# IVSTAGEV2.net
KiCad netlist of a schematic drawn in EAGLE
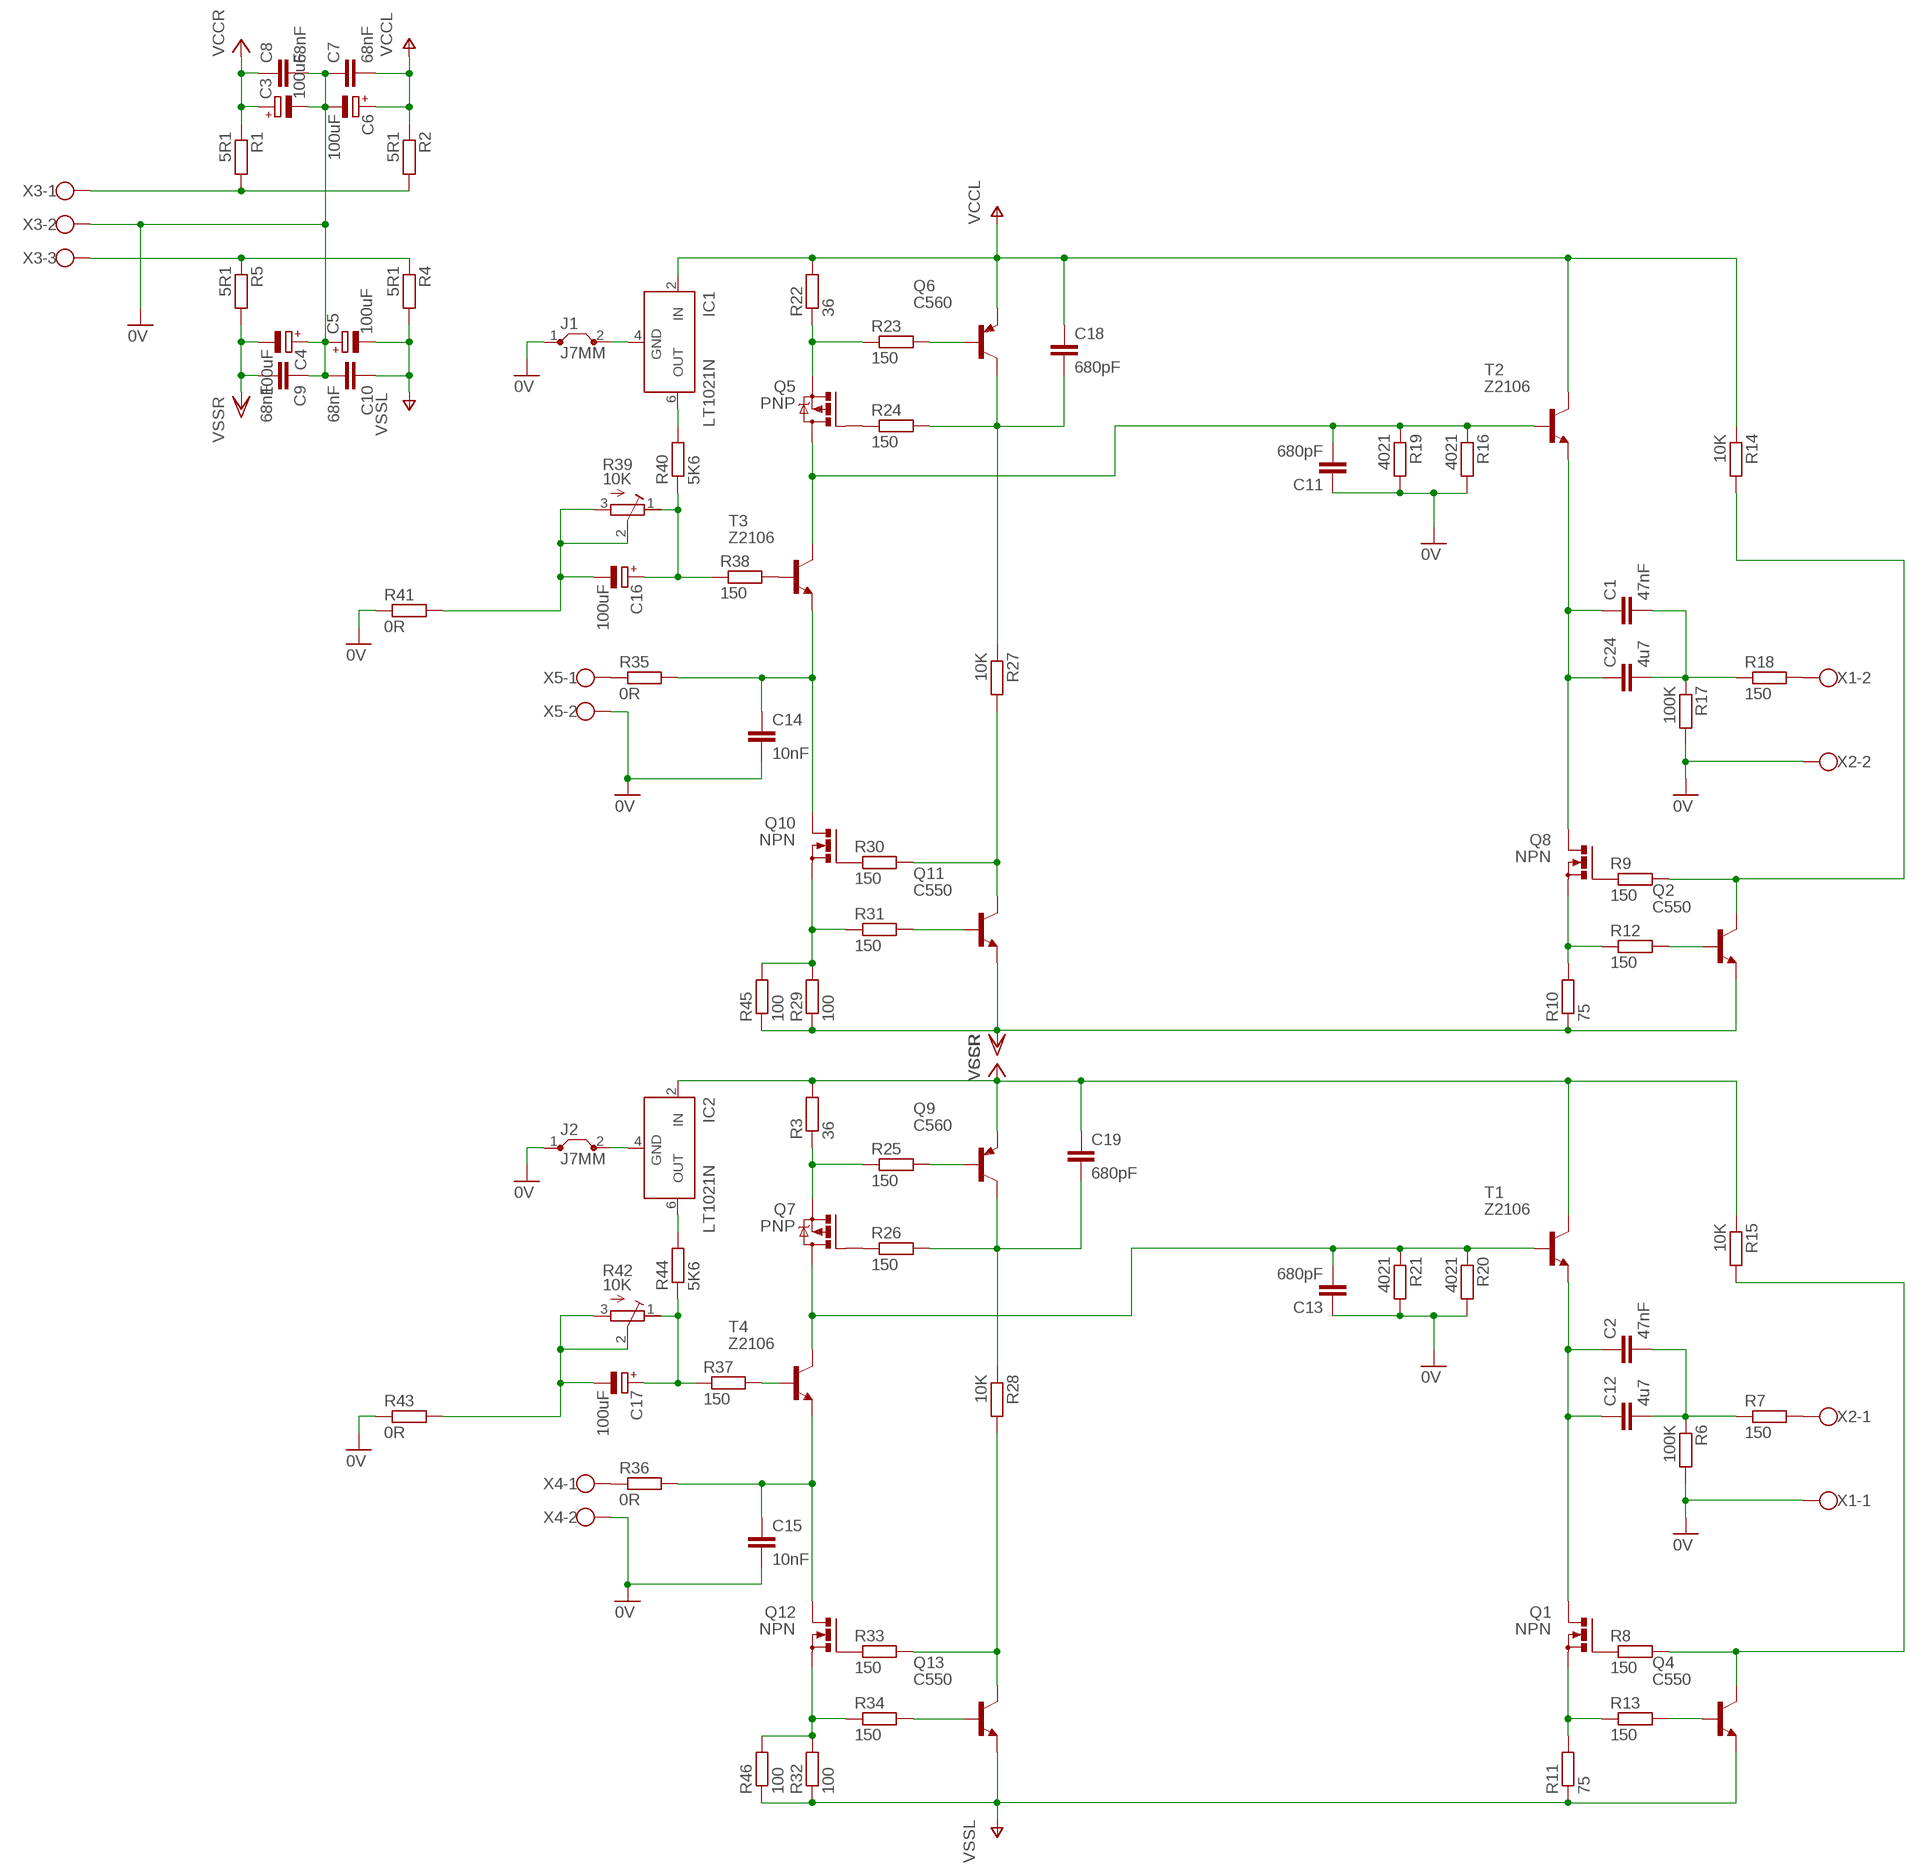
[diagram p0: schematic, sheet 1]

(export (version "E")
  (design (tool "Eeschema 10.0.6"))
  (components
    (comp (ref "C1")
      (value "47nF")
      (footprint "eagle-import:C050-050X075")
      (libsource (lib "eagle-import") (part "C-EU050-050X075"))
    )
    (comp (ref "C2")
      (value "47nF")
      (footprint "eagle-import:C050-050X075")
      (libsource (lib "eagle-import") (part "C-EU050-050X075"))
    )
    (comp (ref "C3")
      (value "100uF")
      (footprint "eagle-import:E5-13")
      (libsource (lib "eagle-import") (part "CPOL-EUE5-13"))
    )
    (comp (ref "C4")
      (value "100uF")
      (footprint "eagle-import:E5-13")
      (libsource (lib "eagle-import") (part "CPOL-EUE5-13"))
    )
    (comp (ref "C5")
      (value "100uF")
      (footprint "eagle-import:E5-13")
      (libsource (lib "eagle-import") (part "CPOL-EUE5-13"))
    )
    (comp (ref "C6")
      (value "100uF")
      (footprint "eagle-import:E5-13")
      (libsource (lib "eagle-import") (part "CPOL-EUE5-13"))
    )
    (comp (ref "C7")
      (value "68nF")
      (footprint "eagle-import:C050-035X075")
      (libsource (lib "eagle-import") (part "C-EU050-035X075"))
    )
    (comp (ref "C8")
      (value "68nF")
      (footprint "eagle-import:C050-035X075")
      (libsource (lib "eagle-import") (part "C-EU050-035X075"))
    )
    (comp (ref "C9")
      (value "68nF")
      (footprint "eagle-import:C050-035X075")
      (libsource (lib "eagle-import") (part "C-EU050-035X075"))
    )
    (comp (ref "C10")
      (value "68nF")
      (footprint "eagle-import:C050-035X075")
      (libsource (lib "eagle-import") (part "C-EU050-035X075"))
    )
    (comp (ref "C11")
      (value "680pF")
      (footprint "eagle-import:C050-035X075")
      (libsource (lib "eagle-import") (part "C-EU050-035X075"))
    )
    (comp (ref "C12")
      (value "4u7")
      (footprint "eagle-import:C37.5B19")
      (libsource (lib "eagle-import") (part "C37/19"))
    )
    (comp (ref "C13")
      (value "680pF")
      (footprint "eagle-import:C050-035X075")
      (libsource (lib "eagle-import") (part "C-EU050-035X075"))
    )
    (comp (ref "C14")
      (value "10nF")
      (footprint "eagle-import:C050-050X075")
      (libsource (lib "eagle-import") (part "C-EU050-050X075"))
    )
    (comp (ref "C15")
      (value "10nF")
      (footprint "eagle-import:C050-050X075")
      (libsource (lib "eagle-import") (part "C-EU050-050X075"))
    )
    (comp (ref "C16")
      (value "100uF")
      (footprint "eagle-import:E5-10,5")
      (libsource (lib "eagle-import") (part "CPOL-EUE5-10.5"))
    )
    (comp (ref "C17")
      (value "100uF")
      (footprint "eagle-import:E5-10,5")
      (libsource (lib "eagle-import") (part "CPOL-EUE5-10.5"))
    )
    (comp (ref "C18")
      (value "680pF")
      (footprint "eagle-import:C050-045X075")
      (libsource (lib "eagle-import") (part "C-EU050-045X075"))
    )
    (comp (ref "C19")
      (value "680pF")
      (footprint "eagle-import:C050-045X075")
      (libsource (lib "eagle-import") (part "C-EU050-045X075"))
    )
    (comp (ref "C24")
      (value "4u7")
      (footprint "eagle-import:C37.5B19")
      (libsource (lib "eagle-import") (part "C37/19"))
    )
    (comp (ref "IC1")
      (value "LT1021N")
      (footprint "eagle-import:DIL08")
      (libsource (lib "eagle-import") (part "LT1021N"))
    )
    (comp (ref "IC2")
      (value "LT1021N")
      (footprint "eagle-import:DIL08")
      (libsource (lib "eagle-import") (part "LT1021N"))
    )
    (comp (ref "J1")
      (value "J7MM")
      (footprint "eagle-import:07")
      (libsource (lib "eagle-import") (part "J7MM"))
    )
    (comp (ref "J2")
      (value "J7MM")
      (footprint "eagle-import:07")
      (libsource (lib "eagle-import") (part "J7MM"))
    )
    (comp (ref "Q1")
      (value "NPN")
      (footprint "eagle-import:TO220BV")
      (libsource (lib "eagle-import") (part "PMOSFET_NTO220BV"))
    )
    (comp (ref "Q2")
      (value "C550")
      (footprint "eagle-import:TO92-EBC")
      (libsource (lib "eagle-import") (part "BC550B"))
    )
    (comp (ref "Q4")
      (value "C550")
      (footprint "eagle-import:TO92-EBC")
      (libsource (lib "eagle-import") (part "BC550B"))
    )
    (comp (ref "Q5")
      (value "PNP")
      (footprint "eagle-import:TO220BV")
      (libsource (lib "eagle-import") (part "IRF9530"))
    )
    (comp (ref "Q6")
      (value "C560")
      (footprint "eagle-import:TO92-EBC")
      (libsource (lib "eagle-import") (part "BC560"))
    )
    (comp (ref "Q7")
      (value "PNP")
      (footprint "eagle-import:TO220BV")
      (libsource (lib "eagle-import") (part "IRF9530"))
    )
    (comp (ref "Q8")
      (value "NPN")
      (footprint "eagle-import:TO220BV")
      (libsource (lib "eagle-import") (part "PMOSFET_NTO220BV"))
    )
    (comp (ref "Q9")
      (value "C560")
      (footprint "eagle-import:TO92-EBC")
      (libsource (lib "eagle-import") (part "BC560"))
    )
    (comp (ref "Q10")
      (value "NPN")
      (footprint "eagle-import:TO220BV")
      (libsource (lib "eagle-import") (part "PMOSFET_NTO220BV"))
    )
    (comp (ref "Q11")
      (value "C550")
      (footprint "eagle-import:TO92-EBC")
      (libsource (lib "eagle-import") (part "BC550B"))
    )
    (comp (ref "Q12")
      (value "NPN")
      (footprint "eagle-import:TO220BV")
      (libsource (lib "eagle-import") (part "PMOSFET_NTO220BV"))
    )
    (comp (ref "Q13")
      (value "C550")
      (footprint "eagle-import:TO92-EBC")
      (libsource (lib "eagle-import") (part "BC550B"))
    )
    (comp (ref "R1")
      (value "5R1")
      (footprint "eagle-import:0207_7")
      (libsource (lib "eagle-import") (part "R-EU_0207/7"))
    )
    (comp (ref "R2")
      (value "5R1")
      (footprint "eagle-import:0207_7")
      (libsource (lib "eagle-import") (part "R-EU_0207/7"))
    )
    (comp (ref "R3")
      (value "36")
      (footprint "eagle-import:0207_7")
      (libsource (lib "eagle-import") (part "R-EU_0207/7"))
    )
    (comp (ref "R4")
      (value "5R1")
      (footprint "eagle-import:0207_7")
      (libsource (lib "eagle-import") (part "R-EU_0207/7"))
    )
    (comp (ref "R5")
      (value "5R1")
      (footprint "eagle-import:0207_7")
      (libsource (lib "eagle-import") (part "R-EU_0207/7"))
    )
    (comp (ref "R6")
      (value "100K")
      (footprint "eagle-import:0204_7")
      (libsource (lib "eagle-import") (part "R-EU_0204/7"))
    )
    (comp (ref "R7")
      (value "150")
      (footprint "eagle-import:0207_7")
      (libsource (lib "eagle-import") (part "R-EU_0207/7"))
    )
    (comp (ref "R8")
      (value "150")
      (footprint "eagle-import:0207_7")
      (libsource (lib "eagle-import") (part "R-EU_0207/7"))
    )
    (comp (ref "R9")
      (value "150")
      (footprint "eagle-import:0207_7")
      (libsource (lib "eagle-import") (part "R-EU_0207/7"))
    )
    (comp (ref "R10")
      (value "75")
      (footprint "eagle-import:0207_7")
      (libsource (lib "eagle-import") (part "R-EU_0207/7"))
    )
    (comp (ref "R11")
      (value "75")
      (footprint "eagle-import:0207_7")
      (libsource (lib "eagle-import") (part "R-EU_0207/7"))
    )
    (comp (ref "R12")
      (value "150")
      (footprint "eagle-import:0207_7")
      (libsource (lib "eagle-import") (part "R-EU_0207/7"))
    )
    (comp (ref "R13")
      (value "150")
      (footprint "eagle-import:0207_7")
      (libsource (lib "eagle-import") (part "R-EU_0207/7"))
    )
    (comp (ref "R14")
      (value "10K")
      (footprint "eagle-import:0309_12")
      (libsource (lib "eagle-import") (part "R-EU_0309/12"))
    )
    (comp (ref "R15")
      (value "10K")
      (footprint "eagle-import:0309_12")
      (libsource (lib "eagle-import") (part "R-EU_0309/12"))
    )
    (comp (ref "R16")
      (value "4021")
      (footprint "eagle-import:0309_12")
      (libsource (lib "eagle-import") (part "R-EU_0309/12"))
    )
    (comp (ref "R17")
      (value "100K")
      (footprint "eagle-import:0204_7")
      (libsource (lib "eagle-import") (part "R-EU_0204/7"))
    )
    (comp (ref "R18")
      (value "150")
      (footprint "eagle-import:0207_7")
      (libsource (lib "eagle-import") (part "R-EU_0207/7"))
    )
    (comp (ref "R19")
      (value "4021")
      (footprint "eagle-import:0309_12")
      (libsource (lib "eagle-import") (part "R-EU_0309/12"))
    )
    (comp (ref "R20")
      (value "4021")
      (footprint "eagle-import:0309_12")
      (libsource (lib "eagle-import") (part "R-EU_0309/12"))
    )
    (comp (ref "R21")
      (value "4021")
      (footprint "eagle-import:0309_12")
      (libsource (lib "eagle-import") (part "R-EU_0309/12"))
    )
    (comp (ref "R22")
      (value "36")
      (footprint "eagle-import:0207_7")
      (libsource (lib "eagle-import") (part "R-EU_0207/7"))
    )
    (comp (ref "R23")
      (value "150")
      (footprint "eagle-import:0207_10")
      (libsource (lib "eagle-import") (part "R-EU_0207/10"))
    )
    (comp (ref "R24")
      (value "150")
      (footprint "eagle-import:0207_7")
      (libsource (lib "eagle-import") (part "R-EU_0207/7"))
    )
    (comp (ref "R25")
      (value "150")
      (footprint "eagle-import:0207_10")
      (libsource (lib "eagle-import") (part "R-EU_0207/10"))
    )
    (comp (ref "R26")
      (value "150")
      (footprint "eagle-import:0207_10")
      (libsource (lib "eagle-import") (part "R-EU_0207/10"))
    )
    (comp (ref "R27")
      (value "10K")
      (footprint "eagle-import:0309_12")
      (libsource (lib "eagle-import") (part "R-EU_0309/12"))
    )
    (comp (ref "R28")
      (value "10K")
      (footprint "eagle-import:0309_12")
      (libsource (lib "eagle-import") (part "R-EU_0309/12"))
    )
    (comp (ref "R29")
      (value "100")
      (footprint "eagle-import:0207_7")
      (libsource (lib "eagle-import") (part "R-EU_0207/7"))
    )
    (comp (ref "R30")
      (value "150")
      (footprint "eagle-import:0207_7")
      (libsource (lib "eagle-import") (part "R-EU_0207/7"))
    )
    (comp (ref "R31")
      (value "150")
      (footprint "eagle-import:0207_7")
      (libsource (lib "eagle-import") (part "R-EU_0207/7"))
    )
    (comp (ref "R32")
      (value "100")
      (footprint "eagle-import:0207_7")
      (libsource (lib "eagle-import") (part "R-EU_0207/7"))
    )
    (comp (ref "R33")
      (value "150")
      (footprint "eagle-import:0207_7")
      (libsource (lib "eagle-import") (part "R-EU_0207/7"))
    )
    (comp (ref "R34")
      (value "150")
      (footprint "eagle-import:0207_7")
      (libsource (lib "eagle-import") (part "R-EU_0207/7"))
    )
    (comp (ref "R35")
      (value "0R")
      (footprint "eagle-import:0207_7")
      (libsource (lib "eagle-import") (part "R-EU_0207/7"))
    )
    (comp (ref "R36")
      (value "0R")
      (footprint "eagle-import:0207_7")
      (libsource (lib "eagle-import") (part "R-EU_0207/7"))
    )
    (comp (ref "R37")
      (value "150")
      (footprint "eagle-import:0204_7")
      (libsource (lib "eagle-import") (part "R-EU_0204/7"))
    )
    (comp (ref "R38")
      (value "150")
      (footprint "eagle-import:0204_7")
      (libsource (lib "eagle-import") (part "R-EU_0204/7"))
    )
    (comp (ref "R39")
      (value "10K")
      (footprint "eagle-import:RTRIMT93YA")
      (libsource (lib "eagle-import") (part "R-TRIMMT93YA"))
    )
    (comp (ref "R40")
      (value "5K6")
      (footprint "eagle-import:0207_10")
      (libsource (lib "eagle-import") (part "R-EU_0207/10"))
    )
    (comp (ref "R41")
      (value "0R")
      (footprint "eagle-import:0207_10")
      (libsource (lib "eagle-import") (part "R-EU_0207/10"))
    )
    (comp (ref "R42")
      (value "10K")
      (footprint "eagle-import:RTRIMT93YA")
      (libsource (lib "eagle-import") (part "R-TRIMMT93YA"))
    )
    (comp (ref "R43")
      (value "0R")
      (footprint "eagle-import:0207_10")
      (libsource (lib "eagle-import") (part "R-EU_0207/10"))
    )
    (comp (ref "R44")
      (value "5K6")
      (footprint "eagle-import:0207_10")
      (libsource (lib "eagle-import") (part "R-EU_0207/10"))
    )
    (comp (ref "R45")
      (value "100")
      (footprint "eagle-import:0207_7")
      (libsource (lib "eagle-import") (part "R-EU_0207/7"))
    )
    (comp (ref "R46")
      (value "100")
      (footprint "eagle-import:0207_7")
      (libsource (lib "eagle-import") (part "R-EU_0207/7"))
    )
    (comp (ref "T1")
      (value "Z2106")
      (footprint "eagle-import:TO92-EBC")
      (libsource (lib "eagle-import") (part "-NPN-TO92-EBCBC337"))
    )
    (comp (ref "T2")
      (value "Z2106")
      (footprint "eagle-import:TO92-EBC")
      (libsource (lib "eagle-import") (part "-NPN-TO92-EBCBC337-40"))
    )
    (comp (ref "T3")
      (value "Z2106")
      (footprint "eagle-import:TO92-EBC")
      (libsource (lib "eagle-import") (part "-NPN-TO92-EBCBC337"))
    )
    (comp (ref "T4")
      (value "Z2106")
      (footprint "eagle-import:TO92-EBC")
      (libsource (lib "eagle-import") (part "-NPN-TO92-EBCBC337-40"))
    )
    (comp (ref "X1")
      (value "W237-02P")
      (footprint "eagle-import:W237-132")
      (libsource (lib "eagle-import") (part "W237-02P"))
    )
    (comp (ref "X2")
      (value "W237-02P")
      (footprint "eagle-import:W237-132")
      (libsource (lib "eagle-import") (part "W237-02P"))
    )
    (comp (ref "X3")
      (value "W237-03P")
      (footprint "eagle-import:W237-133")
      (libsource (lib "eagle-import") (part "W237-03P"))
    )
    (comp (ref "X4")
      (value "W237-02P")
      (footprint "eagle-import:W237-132")
      (libsource (lib "eagle-import") (part "W237-02P"))
    )
    (comp (ref "X5")
      (value "W237-02P")
      (footprint "eagle-import:W237-132")
      (libsource (lib "eagle-import") (part "W237-02P"))
    )
  )
  (nets
    (net (code "1") (name "0V") (class "Default")
      (node (ref "C10") (pin "2") (pinfunction "2_2") (pintype "passive"))
      (node (ref "C11") (pin "1") (pinfunction "1_1") (pintype "passive"))
      (node (ref "C13") (pin "1") (pinfunction "1_1") (pintype "passive"))
      (node (ref "C14") (pin "2") (pinfunction "2_2") (pintype "passive"))
      (node (ref "C15") (pin "2") (pinfunction "2_2") (pintype "passive"))
      (node (ref "C3") (pin "-") (pinfunction "-_-") (pintype "passive"))
      (node (ref "C4") (pin "+") (pinfunction "+_+") (pintype "passive"))
      (node (ref "C5") (pin "+") (pinfunction "+_+") (pintype "passive"))
      (node (ref "C6") (pin "-") (pinfunction "-_-") (pintype "passive"))
      (node (ref "C7") (pin "1") (pinfunction "1_1") (pintype "passive"))
      (node (ref "C8") (pin "2") (pinfunction "2_2") (pintype "passive"))
      (node (ref "C9") (pin "1") (pinfunction "1_1") (pintype "passive"))
      (node (ref "J1") (pin "1") (pinfunction "1_1") (pintype "passive"))
      (node (ref "J2") (pin "1") (pinfunction "1_1") (pintype "passive"))
      (node (ref "R16") (pin "2") (pinfunction "2_2") (pintype "passive"))
      (node (ref "R17") (pin "2") (pinfunction "2_2") (pintype "passive"))
      (node (ref "R19") (pin "2") (pinfunction "2_2") (pintype "passive"))
      (node (ref "R20") (pin "2") (pinfunction "2_2") (pintype "passive"))
      (node (ref "R21") (pin "2") (pinfunction "2_2") (pintype "passive"))
      (node (ref "R41") (pin "1") (pinfunction "1_1") (pintype "passive"))
      (node (ref "R43") (pin "1") (pinfunction "1_1") (pintype "passive"))
      (node (ref "R6") (pin "2") (pinfunction "2_2") (pintype "passive"))
      (node (ref "X1") (pin "1") (pinfunction "KL_1") (pintype "passive"))
      (node (ref "X2") (pin "2") (pinfunction "KL_2") (pintype "passive"))
      (node (ref "X3") (pin "2") (pinfunction "KL_2") (pintype "passive"))
      (node (ref "X4") (pin "2") (pinfunction "KL_2") (pintype "passive"))
      (node (ref "X5") (pin "2") (pinfunction "KL_2") (pintype "passive"))
    )
    (net (code "2") (name "Net-(C1-Pad1)") (class "Default")
      (node (ref "C1") (pin "1") (pinfunction "1_1") (pintype "passive"))
      (node (ref "C24") (pin "1") (pinfunction "1_1") (pintype "passive"))
      (node (ref "Q8") (pin "D") (pinfunction "D_D") (pintype "passive"))
      (node (ref "T2") (pin "E") (pinfunction "E_E") (pintype "passive"))
    )
    (net (code "3") (name "Net-(C1-Pad2)") (class "Default")
      (node (ref "C1") (pin "2") (pinfunction "2_2") (pintype "passive"))
      (node (ref "C24") (pin "2") (pinfunction "2_2") (pintype "passive"))
      (node (ref "R17") (pin "1") (pinfunction "1_1") (pintype "passive"))
      (node (ref "R18") (pin "1") (pinfunction "1_1") (pintype "passive"))
    )
    (net (code "4") (name "Net-(C11-Pad2)") (class "Default")
      (node (ref "C11") (pin "2") (pinfunction "2_2") (pintype "passive"))
      (node (ref "Q5") (pin "D") (pinfunction "D_D") (pintype "passive"))
      (node (ref "R16") (pin "1") (pinfunction "1_1") (pintype "passive"))
      (node (ref "R19") (pin "1") (pinfunction "1_1") (pintype "passive"))
      (node (ref "T2") (pin "B") (pinfunction "B_B") (pintype "passive"))
      (node (ref "T3") (pin "C") (pinfunction "C_C") (pintype "passive"))
    )
    (net (code "5") (name "Net-(C12-Pad1)") (class "Default")
      (node (ref "C12") (pin "1") (pinfunction "1_1") (pintype "passive"))
      (node (ref "C2") (pin "1") (pinfunction "1_1") (pintype "passive"))
      (node (ref "Q1") (pin "D") (pinfunction "D_D") (pintype "passive"))
      (node (ref "T1") (pin "E") (pinfunction "E_E") (pintype "passive"))
    )
    (net (code "6") (name "Net-(C12-Pad2)") (class "Default")
      (node (ref "C12") (pin "2") (pinfunction "2_2") (pintype "passive"))
      (node (ref "C2") (pin "2") (pinfunction "2_2") (pintype "passive"))
      (node (ref "R6") (pin "1") (pinfunction "1_1") (pintype "passive"))
      (node (ref "R7") (pin "1") (pinfunction "1_1") (pintype "passive"))
    )
    (net (code "7") (name "Net-(C13-Pad2)") (class "Default")
      (node (ref "C13") (pin "2") (pinfunction "2_2") (pintype "passive"))
      (node (ref "Q7") (pin "D") (pinfunction "D_D") (pintype "passive"))
      (node (ref "R20") (pin "1") (pinfunction "1_1") (pintype "passive"))
      (node (ref "R21") (pin "1") (pinfunction "1_1") (pintype "passive"))
      (node (ref "T1") (pin "B") (pinfunction "B_B") (pintype "passive"))
      (node (ref "T4") (pin "C") (pinfunction "C_C") (pintype "passive"))
    )
    (net (code "8") (name "Net-(C14-Pad1)") (class "Default")
      (node (ref "C14") (pin "1") (pinfunction "1_1") (pintype "passive"))
      (node (ref "Q10") (pin "D") (pinfunction "D_D") (pintype "passive"))
      (node (ref "R35") (pin "2") (pinfunction "2_2") (pintype "passive"))
      (node (ref "T3") (pin "E") (pinfunction "E_E") (pintype "passive"))
    )
    (net (code "9") (name "Net-(C15-Pad1)") (class "Default")
      (node (ref "C15") (pin "1") (pinfunction "1_1") (pintype "passive"))
      (node (ref "Q12") (pin "D") (pinfunction "D_D") (pintype "passive"))
      (node (ref "R36") (pin "2") (pinfunction "2_2") (pintype "passive"))
      (node (ref "T4") (pin "E") (pinfunction "E_E") (pintype "passive"))
    )
    (net (code "10") (name "Net-(C18-Pad2)") (class "Default")
      (node (ref "C18") (pin "2") (pinfunction "2_2") (pintype "passive"))
      (node (ref "Q6") (pin "C") (pinfunction "C_C") (pintype "passive"))
      (node (ref "R24") (pin "2") (pinfunction "2_2") (pintype "passive"))
      (node (ref "R27") (pin "1") (pinfunction "1_1") (pintype "passive"))
    )
    (net (code "11") (name "Net-(C19-Pad2)") (class "Default")
      (node (ref "C19") (pin "2") (pinfunction "2_2") (pintype "passive"))
      (node (ref "Q9") (pin "C") (pinfunction "C_C") (pintype "passive"))
      (node (ref "R26") (pin "2") (pinfunction "2_2") (pintype "passive"))
      (node (ref "R28") (pin "1") (pinfunction "1_1") (pintype "passive"))
    )
    (net (code "12") (name "Net-(IC1-GND)") (class "Default")
      (node (ref "IC1") (pin "4") (pinfunction "GND_4") (pintype "power_in"))
      (node (ref "J1") (pin "2") (pinfunction "2_2") (pintype "passive"))
    )
    (net (code "13") (name "Net-(IC1-OUT)") (class "Default")
      (node (ref "IC1") (pin "6") (pinfunction "OUT_6") (pintype "output"))
      (node (ref "R40") (pin "2") (pinfunction "2_2") (pintype "passive"))
    )
    (net (code "14") (name "Net-(IC2-GND)") (class "Default")
      (node (ref "IC2") (pin "4") (pinfunction "GND_4") (pintype "power_in"))
      (node (ref "J2") (pin "2") (pinfunction "2_2") (pintype "passive"))
    )
    (net (code "15") (name "Net-(IC2-OUT)") (class "Default")
      (node (ref "IC2") (pin "6") (pinfunction "OUT_6") (pintype "output"))
      (node (ref "R44") (pin "2") (pinfunction "2_2") (pintype "passive"))
    )
    (net (code "16") (name "Net-(Q1-PadG)") (class "Default")
      (node (ref "Q1") (pin "G") (pinfunction "G_G") (pintype "passive"))
      (node (ref "R8") (pin "1") (pinfunction "1_1") (pintype "passive"))
    )
    (net (code "17") (name "Net-(Q1-PadS)") (class "Default")
      (node (ref "Q1") (pin "S") (pinfunction "S_S") (pintype "passive"))
      (node (ref "R11") (pin "2") (pinfunction "2_2") (pintype "passive"))
      (node (ref "R13") (pin "1") (pinfunction "1_1") (pintype "passive"))
    )
    (net (code "18") (name "Net-(Q2-PadB)") (class "Default")
      (node (ref "Q2") (pin "B") (pinfunction "B_B") (pintype "passive"))
      (node (ref "R12") (pin "2") (pinfunction "2_2") (pintype "passive"))
    )
    (net (code "19") (name "Net-(Q2-PadC)") (class "Default")
      (node (ref "Q2") (pin "C") (pinfunction "C_C") (pintype "passive"))
      (node (ref "R14") (pin "2") (pinfunction "2_2") (pintype "passive"))
      (node (ref "R9") (pin "2") (pinfunction "2_2") (pintype "passive"))
    )
    (net (code "20") (name "Net-(Q4-PadB)") (class "Default")
      (node (ref "Q4") (pin "B") (pinfunction "B_B") (pintype "passive"))
      (node (ref "R13") (pin "2") (pinfunction "2_2") (pintype "passive"))
    )
    (net (code "21") (name "Net-(Q4-PadC)") (class "Default")
      (node (ref "Q4") (pin "C") (pinfunction "C_C") (pintype "passive"))
      (node (ref "R15") (pin "2") (pinfunction "2_2") (pintype "passive"))
      (node (ref "R8") (pin "2") (pinfunction "2_2") (pintype "passive"))
    )
    (net (code "22") (name "Net-(Q5-PadG)") (class "Default")
      (node (ref "Q5") (pin "G") (pinfunction "G_G") (pintype "passive"))
      (node (ref "R24") (pin "1") (pinfunction "1_1") (pintype "passive"))
    )
    (net (code "23") (name "Net-(Q5-PadS)") (class "Default")
      (node (ref "Q5") (pin "S") (pinfunction "S_S") (pintype "passive"))
      (node (ref "R22") (pin "1") (pinfunction "1_1") (pintype "passive"))
      (node (ref "R23") (pin "1") (pinfunction "1_1") (pintype "passive"))
    )
    (net (code "24") (name "Net-(Q6-PadB)") (class "Default")
      (node (ref "Q6") (pin "B") (pinfunction "B_B") (pintype "passive"))
      (node (ref "R23") (pin "2") (pinfunction "2_2") (pintype "passive"))
    )
    (net (code "25") (name "Net-(Q7-PadG)") (class "Default")
      (node (ref "Q7") (pin "G") (pinfunction "G_G") (pintype "passive"))
      (node (ref "R26") (pin "1") (pinfunction "1_1") (pintype "passive"))
    )
    (net (code "26") (name "Net-(Q7-PadS)") (class "Default")
      (node (ref "Q7") (pin "S") (pinfunction "S_S") (pintype "passive"))
      (node (ref "R25") (pin "1") (pinfunction "1_1") (pintype "passive"))
      (node (ref "R3") (pin "1") (pinfunction "1_1") (pintype "passive"))
    )
    (net (code "27") (name "Net-(Q8-PadG)") (class "Default")
      (node (ref "Q8") (pin "G") (pinfunction "G_G") (pintype "passive"))
      (node (ref "R9") (pin "1") (pinfunction "1_1") (pintype "passive"))
    )
    (net (code "28") (name "Net-(Q8-PadS)") (class "Default")
      (node (ref "Q8") (pin "S") (pinfunction "S_S") (pintype "passive"))
      (node (ref "R10") (pin "2") (pinfunction "2_2") (pintype "passive"))
      (node (ref "R12") (pin "1") (pinfunction "1_1") (pintype "passive"))
    )
    (net (code "29") (name "Net-(Q9-PadB)") (class "Default")
      (node (ref "Q9") (pin "B") (pinfunction "B_B") (pintype "passive"))
      (node (ref "R25") (pin "2") (pinfunction "2_2") (pintype "passive"))
    )
    (net (code "30") (name "Net-(Q10-PadG)") (class "Default")
      (node (ref "Q10") (pin "G") (pinfunction "G_G") (pintype "passive"))
      (node (ref "R30") (pin "1") (pinfunction "1_1") (pintype "passive"))
    )
    (net (code "31") (name "Net-(Q10-PadS)") (class "Default")
      (node (ref "Q10") (pin "S") (pinfunction "S_S") (pintype "passive"))
      (node (ref "R29") (pin "2") (pinfunction "2_2") (pintype "passive"))
      (node (ref "R31") (pin "1") (pinfunction "1_1") (pintype "passive"))
      (node (ref "R45") (pin "2") (pinfunction "2_2") (pintype "passive"))
    )
    (net (code "32") (name "Net-(Q11-PadB)") (class "Default")
      (node (ref "Q11") (pin "B") (pinfunction "B_B") (pintype "passive"))
      (node (ref "R31") (pin "2") (pinfunction "2_2") (pintype "passive"))
    )
    (net (code "33") (name "Net-(Q11-PadC)") (class "Default")
      (node (ref "Q11") (pin "C") (pinfunction "C_C") (pintype "passive"))
      (node (ref "R27") (pin "2") (pinfunction "2_2") (pintype "passive"))
      (node (ref "R30") (pin "2") (pinfunction "2_2") (pintype "passive"))
    )
    (net (code "34") (name "Net-(Q12-PadG)") (class "Default")
      (node (ref "Q12") (pin "G") (pinfunction "G_G") (pintype "passive"))
      (node (ref "R33") (pin "1") (pinfunction "1_1") (pintype "passive"))
    )
    (net (code "35") (name "Net-(Q12-PadS)") (class "Default")
      (node (ref "Q12") (pin "S") (pinfunction "S_S") (pintype "passive"))
      (node (ref "R32") (pin "2") (pinfunction "2_2") (pintype "passive"))
      (node (ref "R34") (pin "1") (pinfunction "1_1") (pintype "passive"))
      (node (ref "R46") (pin "2") (pinfunction "2_2") (pintype "passive"))
    )
    (net (code "36") (name "Net-(Q13-PadB)") (class "Default")
      (node (ref "Q13") (pin "B") (pinfunction "B_B") (pintype "passive"))
      (node (ref "R34") (pin "2") (pinfunction "2_2") (pintype "passive"))
    )
    (net (code "37") (name "Net-(Q13-PadC)") (class "Default")
      (node (ref "Q13") (pin "C") (pinfunction "C_C") (pintype "passive"))
      (node (ref "R28") (pin "2") (pinfunction "2_2") (pintype "passive"))
      (node (ref "R33") (pin "2") (pinfunction "2_2") (pintype "passive"))
    )
    (net (code "38") (name "Net-(R37-Pad2)") (class "Default")
      (node (ref "R37") (pin "2") (pinfunction "2_2") (pintype "passive"))
      (node (ref "T4") (pin "B") (pinfunction "B_B") (pintype "passive"))
    )
    (net (code "39") (name "Net-(R38-Pad2)") (class "Default")
      (node (ref "R38") (pin "2") (pinfunction "2_2") (pintype "passive"))
      (node (ref "T3") (pin "B") (pinfunction "B_B") (pintype "passive"))
    )
    (net (code "40") (name "Net-(R39-A)") (class "Default")
      (node (ref "C16") (pin "+") (pinfunction "+_+") (pintype "passive"))
      (node (ref "R38") (pin "1") (pinfunction "1_1") (pintype "passive"))
      (node (ref "R39") (pin "1") (pinfunction "A_1") (pintype "passive"))
      (node (ref "R40") (pin "1") (pinfunction "1_1") (pintype "passive"))
    )
    (net (code "41") (name "Net-(R39-E)") (class "Default")
      (node (ref "C16") (pin "-") (pinfunction "-_-") (pintype "passive"))
      (node (ref "R39") (pin "2") (pinfunction "S_2") (pintype "passive"))
      (node (ref "R39") (pin "3") (pinfunction "E_3") (pintype "passive"))
      (node (ref "R41") (pin "2") (pinfunction "2_2") (pintype "passive"))
    )
    (net (code "42") (name "Net-(R42-A)") (class "Default")
      (node (ref "C17") (pin "+") (pinfunction "+_+") (pintype "passive"))
      (node (ref "R37") (pin "1") (pinfunction "1_1") (pintype "passive"))
      (node (ref "R42") (pin "1") (pinfunction "A_1") (pintype "passive"))
      (node (ref "R44") (pin "1") (pinfunction "1_1") (pintype "passive"))
    )
    (net (code "43") (name "Net-(R42-E)") (class "Default")
      (node (ref "C17") (pin "-") (pinfunction "-_-") (pintype "passive"))
      (node (ref "R42") (pin "2") (pinfunction "S_2") (pintype "passive"))
      (node (ref "R42") (pin "3") (pinfunction "E_3") (pintype "passive"))
      (node (ref "R43") (pin "2") (pinfunction "2_2") (pintype "passive"))
    )
    (net (code "44") (name "Net-(X1B-KL)") (class "Default")
      (node (ref "R18") (pin "2") (pinfunction "2_2") (pintype "passive"))
      (node (ref "X1") (pin "2") (pinfunction "KL_2") (pintype "passive"))
    )
    (net (code "45") (name "Net-(X2A-KL)") (class "Default")
      (node (ref "R7") (pin "2") (pinfunction "2_2") (pintype "passive"))
      (node (ref "X2") (pin "1") (pinfunction "KL_1") (pintype "passive"))
    )
    (net (code "46") (name "Net-(X3A-KL)") (class "Default")
      (node (ref "R1") (pin "2") (pinfunction "2_2") (pintype "passive"))
      (node (ref "R2") (pin "2") (pinfunction "2_2") (pintype "passive"))
      (node (ref "X3") (pin "1") (pinfunction "KL_1") (pintype "passive"))
    )
    (net (code "47") (name "Net-(X3C-KL)") (class "Default")
      (node (ref "R4") (pin "1") (pinfunction "1_1") (pintype "passive"))
      (node (ref "R5") (pin "1") (pinfunction "1_1") (pintype "passive"))
      (node (ref "X3") (pin "3") (pinfunction "KL_3") (pintype "passive"))
    )
    (net (code "48") (name "Net-(X4A-KL)") (class "Default")
      (node (ref "R36") (pin "1") (pinfunction "1_1") (pintype "passive"))
      (node (ref "X4") (pin "1") (pinfunction "KL_1") (pintype "passive"))
    )
    (net (code "49") (name "Net-(X5A-KL)") (class "Default")
      (node (ref "R35") (pin "1") (pinfunction "1_1") (pintype "passive"))
      (node (ref "X5") (pin "1") (pinfunction "KL_1") (pintype "passive"))
    )
    (net (code "50") (name "VCCL") (class "Default")
      (node (ref "C18") (pin "1") (pinfunction "1_1") (pintype "passive"))
      (node (ref "C6") (pin "+") (pinfunction "+_+") (pintype "passive"))
      (node (ref "C7") (pin "2") (pinfunction "2_2") (pintype "passive"))
      (node (ref "IC1") (pin "2") (pinfunction "IN_2") (pintype "input"))
      (node (ref "Q6") (pin "E") (pinfunction "E_E") (pintype "passive"))
      (node (ref "R14") (pin "1") (pinfunction "1_1") (pintype "passive"))
      (node (ref "R2") (pin "1") (pinfunction "1_1") (pintype "passive"))
      (node (ref "R22") (pin "2") (pinfunction "2_2") (pintype "passive"))
      (node (ref "T2") (pin "C") (pinfunction "C_C") (pintype "passive"))
    )
    (net (code "51") (name "VCCR") (class "Default")
      (node (ref "C19") (pin "1") (pinfunction "1_1") (pintype "passive"))
      (node (ref "C3") (pin "+") (pinfunction "+_+") (pintype "passive"))
      (node (ref "C8") (pin "1") (pinfunction "1_1") (pintype "passive"))
      (node (ref "IC2") (pin "2") (pinfunction "IN_2") (pintype "input"))
      (node (ref "Q9") (pin "E") (pinfunction "E_E") (pintype "passive"))
      (node (ref "R1") (pin "1") (pinfunction "1_1") (pintype "passive"))
      (node (ref "R15") (pin "1") (pinfunction "1_1") (pintype "passive"))
      (node (ref "R3") (pin "2") (pinfunction "2_2") (pintype "passive"))
      (node (ref "T1") (pin "C") (pinfunction "C_C") (pintype "passive"))
    )
    (net (code "52") (name "VSSL") (class "Default")
      (node (ref "C10") (pin "1") (pinfunction "1_1") (pintype "passive"))
      (node (ref "C5") (pin "-") (pinfunction "-_-") (pintype "passive"))
      (node (ref "Q13") (pin "E") (pinfunction "E_E") (pintype "passive"))
      (node (ref "Q4") (pin "E") (pinfunction "E_E") (pintype "passive"))
      (node (ref "R11") (pin "1") (pinfunction "1_1") (pintype "passive"))
      (node (ref "R32") (pin "1") (pinfunction "1_1") (pintype "passive"))
      (node (ref "R4") (pin "2") (pinfunction "2_2") (pintype "passive"))
      (node (ref "R46") (pin "1") (pinfunction "1_1") (pintype "passive"))
    )
    (net (code "53") (name "VSSR") (class "Default")
      (node (ref "C4") (pin "-") (pinfunction "-_-") (pintype "passive"))
      (node (ref "C9") (pin "2") (pinfunction "2_2") (pintype "passive"))
      (node (ref "Q11") (pin "E") (pinfunction "E_E") (pintype "passive"))
      (node (ref "Q2") (pin "E") (pinfunction "E_E") (pintype "passive"))
      (node (ref "R10") (pin "1") (pinfunction "1_1") (pintype "passive"))
      (node (ref "R29") (pin "1") (pinfunction "1_1") (pintype "passive"))
      (node (ref "R45") (pin "1") (pinfunction "1_1") (pintype "passive"))
      (node (ref "R5") (pin "2") (pinfunction "2_2") (pintype "passive"))
    )
  )
)
